# config-bank4.net
KiCad netlist of a schematic drawn in Altium Designer
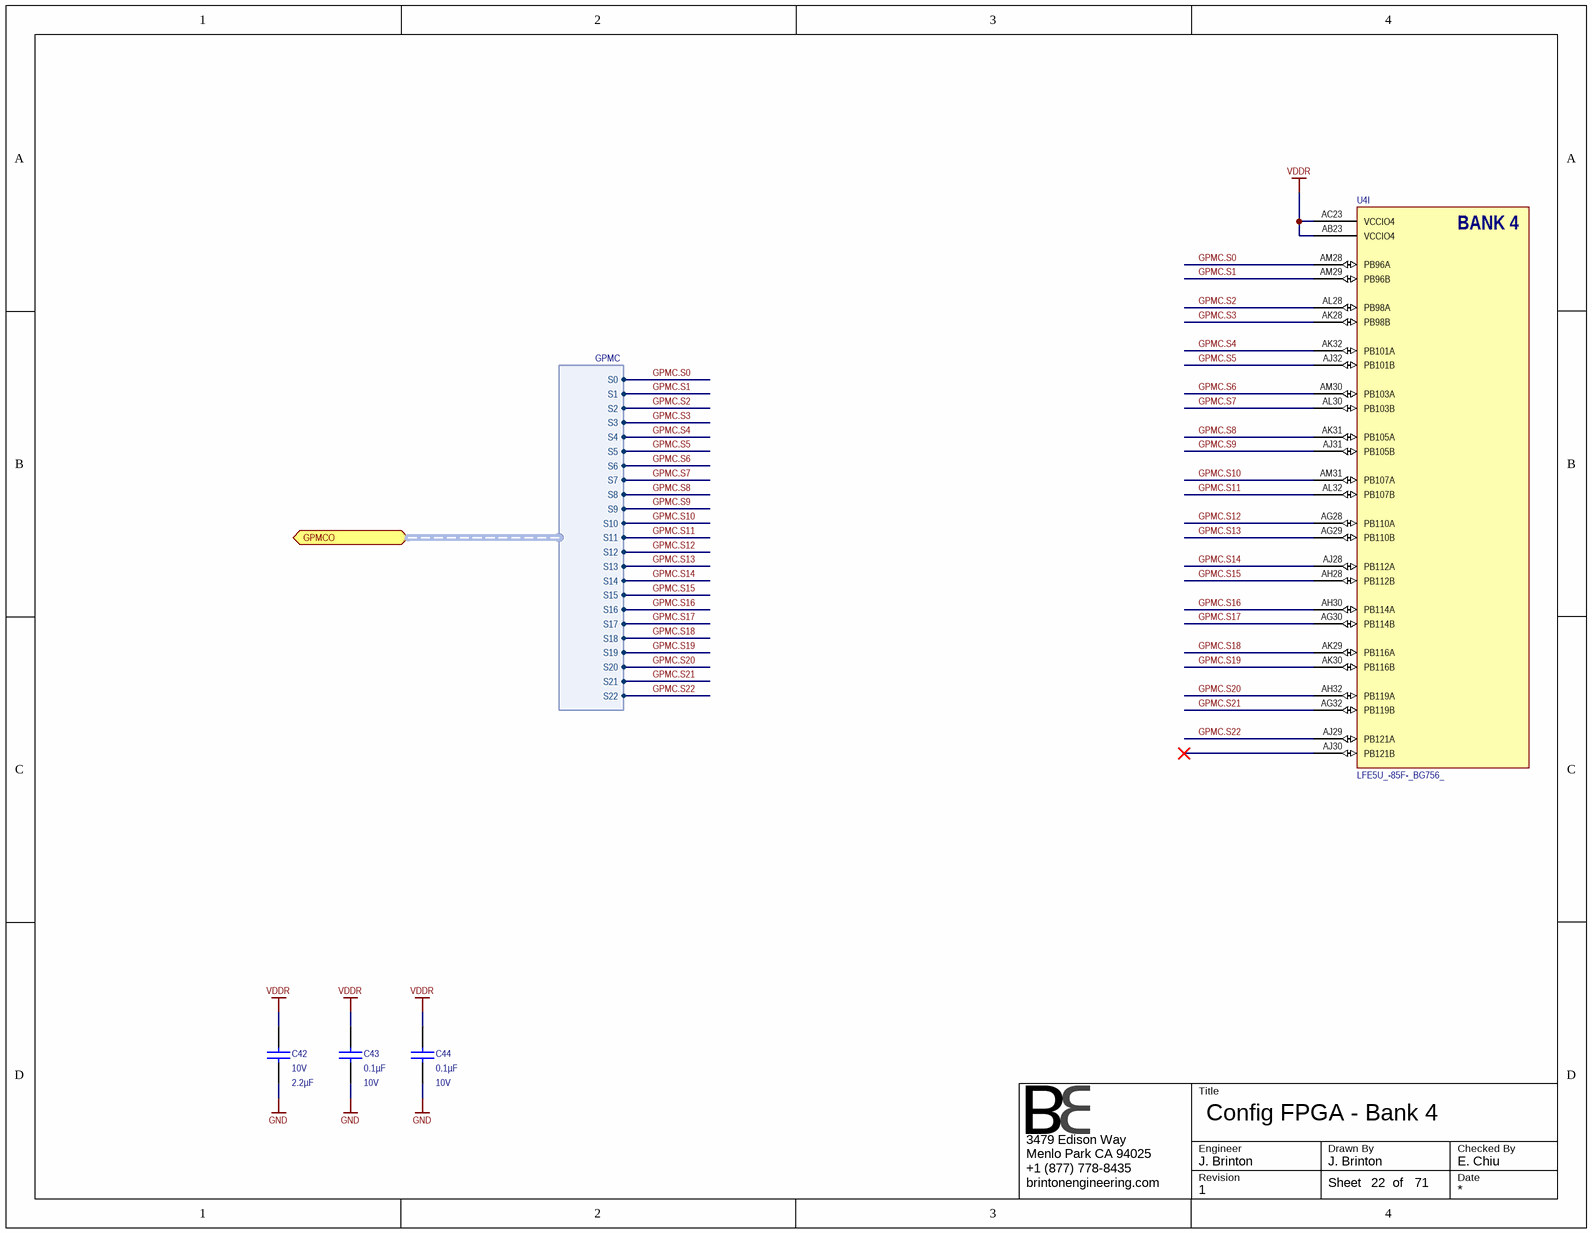
[diagram p0: config-bank4.SchDoc]

(export (version "E")
  (design (tool "Eeschema 10.0.6"))
  (components
    (comp (ref "C42")
      (value "GRM188R71A225KE15D")
      (footprint "CAPC1608X90N")
      (description "CAP CER 2.2UF 10V 10% X7R 0603")
      (fields
        (field (name "MANUFACTURER") "Murata Electronics North America")
        (field (name "TOLERANCE") "±10%")
        (field (name "VOLTAGE - RATED") "10V")
        (field (name "CAPACITANCE") "2.2µF")
      )
      (libsource (lib "murata") (part "GRM188R71A225KE15D"))
    )
    (comp (ref "C43")
      (value "GRM155R71A104KA01J")
      (footprint "CAPC1005X56N")
      (description "CAP CER 0.1UF 10V 10% X7R 0402")
      (fields
        (field (name "MANUFACTURER") "Murata Electronics North America")
        (field (name "TOLERANCE") "±10%")
        (field (name "CAPACITANCE") "0.1µF")
        (field (name "VOLTAGE - RATED") "10V")
      )
      (libsource (lib "murata") (part "GRM155R71A104KA01J"))
    )
    (comp (ref "C44")
      (value "GRM155R71A104KA01J")
      (footprint "CAPC1005X56N")
      (description "CAP CER 0.1UF 10V 10% X7R 0402")
      (fields
        (field (name "MANUFACTURER") "Murata Electronics North America")
        (field (name "TOLERANCE") "±10%")
        (field (name "CAPACITANCE") "0.1µF")
        (field (name "VOLTAGE - RATED") "10V")
      )
      (libsource (lib "murata") (part "GRM155R71A104KA01J"))
    )
    (comp (ref "U4")
      (value "LFE5U_-85F-_BG756_")
      (footprint "lattice:caBGA756")
      (description "ECP5 FPGA, 85k LUT, 756-caBGA")
      (fields (field (name "MANUFACTURER") "Lattice Semiconductor"))
      (libsource (lib "lattice") (part "LFE5U_-85F-_BG756_"))
    )
  )
  (nets
    (net (code "2") (name "/GPMC.S0") (class "Default")
      (node (ref "U4") (pin "AM28") (pinfunction "PB96A_AM28") (pintype "bidirectional"))
    )
    (net (code "3") (name "/GPMC.S1") (class "Default")
      (node (ref "U4") (pin "AM29") (pinfunction "PB96B_AM29") (pintype "bidirectional"))
    )
    (net (code "4") (name "/GPMC.S2") (class "Default")
      (node (ref "U4") (pin "AL28") (pinfunction "PB98A_AL28") (pintype "bidirectional"))
    )
    (net (code "5") (name "/GPMC.S3") (class "Default")
      (node (ref "U4") (pin "AK28") (pinfunction "PB98B_AK28") (pintype "bidirectional"))
    )
    (net (code "6") (name "/GPMC.S4") (class "Default")
      (node (ref "U4") (pin "AK32") (pinfunction "PB101A_AK32") (pintype "bidirectional"))
    )
    (net (code "7") (name "/GPMC.S5") (class "Default")
      (node (ref "U4") (pin "AJ32") (pinfunction "PB101B_AJ32") (pintype "bidirectional"))
    )
    (net (code "8") (name "/GPMC.S6") (class "Default")
      (node (ref "U4") (pin "AM30") (pinfunction "PB103A_AM30") (pintype "bidirectional"))
    )
    (net (code "9") (name "/GPMC.S7") (class "Default")
      (node (ref "U4") (pin "AL30") (pinfunction "PB103B_AL30") (pintype "bidirectional"))
    )
    (net (code "10") (name "/GPMC.S8") (class "Default")
      (node (ref "U4") (pin "AK31") (pinfunction "PB105A_AK31") (pintype "bidirectional"))
    )
    (net (code "11") (name "/GPMC.S9") (class "Default")
      (node (ref "U4") (pin "AJ31") (pinfunction "PB105B_AJ31") (pintype "bidirectional"))
    )
    (net (code "12") (name "/GPMC.S10") (class "Default")
      (node (ref "U4") (pin "AM31") (pinfunction "PB107A_AM31") (pintype "bidirectional"))
    )
    (net (code "13") (name "/GPMC.S11") (class "Default")
      (node (ref "U4") (pin "AL32") (pinfunction "PB107B_AL32") (pintype "bidirectional"))
    )
    (net (code "14") (name "/GPMC.S12") (class "Default")
      (node (ref "U4") (pin "AG28") (pinfunction "PB110A_AG28") (pintype "bidirectional"))
    )
    (net (code "15") (name "/GPMC.S13") (class "Default")
      (node (ref "U4") (pin "AG29") (pinfunction "PB110B_AG29") (pintype "bidirectional"))
    )
    (net (code "16") (name "/GPMC.S14") (class "Default")
      (node (ref "U4") (pin "AJ28") (pinfunction "PB112A_AJ28") (pintype "bidirectional"))
    )
    (net (code "17") (name "/GPMC.S15") (class "Default")
      (node (ref "U4") (pin "AH28") (pinfunction "PB112B_AH28") (pintype "bidirectional"))
    )
    (net (code "18") (name "/GPMC.S16") (class "Default")
      (node (ref "U4") (pin "AH30") (pinfunction "PB114A_AH30") (pintype "bidirectional"))
    )
    (net (code "19") (name "/GPMC.S17") (class "Default")
      (node (ref "U4") (pin "AG30") (pinfunction "PB114B_AG30") (pintype "bidirectional"))
    )
    (net (code "20") (name "/GPMC.S18") (class "Default")
      (node (ref "U4") (pin "AK29") (pinfunction "PB116A_AK29") (pintype "bidirectional"))
    )
    (net (code "21") (name "/GPMC.S19") (class "Default")
      (node (ref "U4") (pin "AK30") (pinfunction "PB116B_AK30") (pintype "bidirectional"))
    )
    (net (code "22") (name "/GPMC.S20") (class "Default")
      (node (ref "U4") (pin "AH32") (pinfunction "PB119A_AH32") (pintype "bidirectional"))
    )
    (net (code "23") (name "/GPMC.S21") (class "Default")
      (node (ref "U4") (pin "AG32") (pinfunction "PB119B_AG32") (pintype "bidirectional"))
    )
    (net (code "24") (name "/GPMC.S22") (class "Default")
      (node (ref "U4") (pin "AJ29") (pinfunction "PB121A_AJ29") (pintype "bidirectional"))
    )
    (net (code "26") (name "GND") (class "Default")
      (node (ref "C42") (pin "1") (pinfunction "1_1") (pintype "passive"))
      (node (ref "C43") (pin "1") (pinfunction "1_1") (pintype "passive"))
      (node (ref "C44") (pin "1") (pinfunction "1_1") (pintype "passive"))
    )
    (net (code "27") (name "VDDR") (class "Default")
      (node (ref "C42") (pin "2") (pinfunction "2_2") (pintype "passive"))
      (node (ref "C43") (pin "2") (pinfunction "2_2") (pintype "passive"))
      (node (ref "C44") (pin "2") (pinfunction "2_2") (pintype "passive"))
      (node (ref "U4") (pin "AB23") (pinfunction "VCCIO4_AB23") (pintype "power_in"))
      (node (ref "U4") (pin "AC23") (pinfunction "VCCIO4_AC23") (pintype "power_in"))
    )
    (net (code "28") (name "unconnected-(U4I-PB121B-PadAJ30)") (class "Default")
      (node (ref "U4") (pin "AJ30") (pinfunction "PB121B_AJ30") (pintype "bidirectional+no_connect"))
    )
  )
)
